# Sheet1.net
KiCad netlist of a schematic drawn in Altium Designer
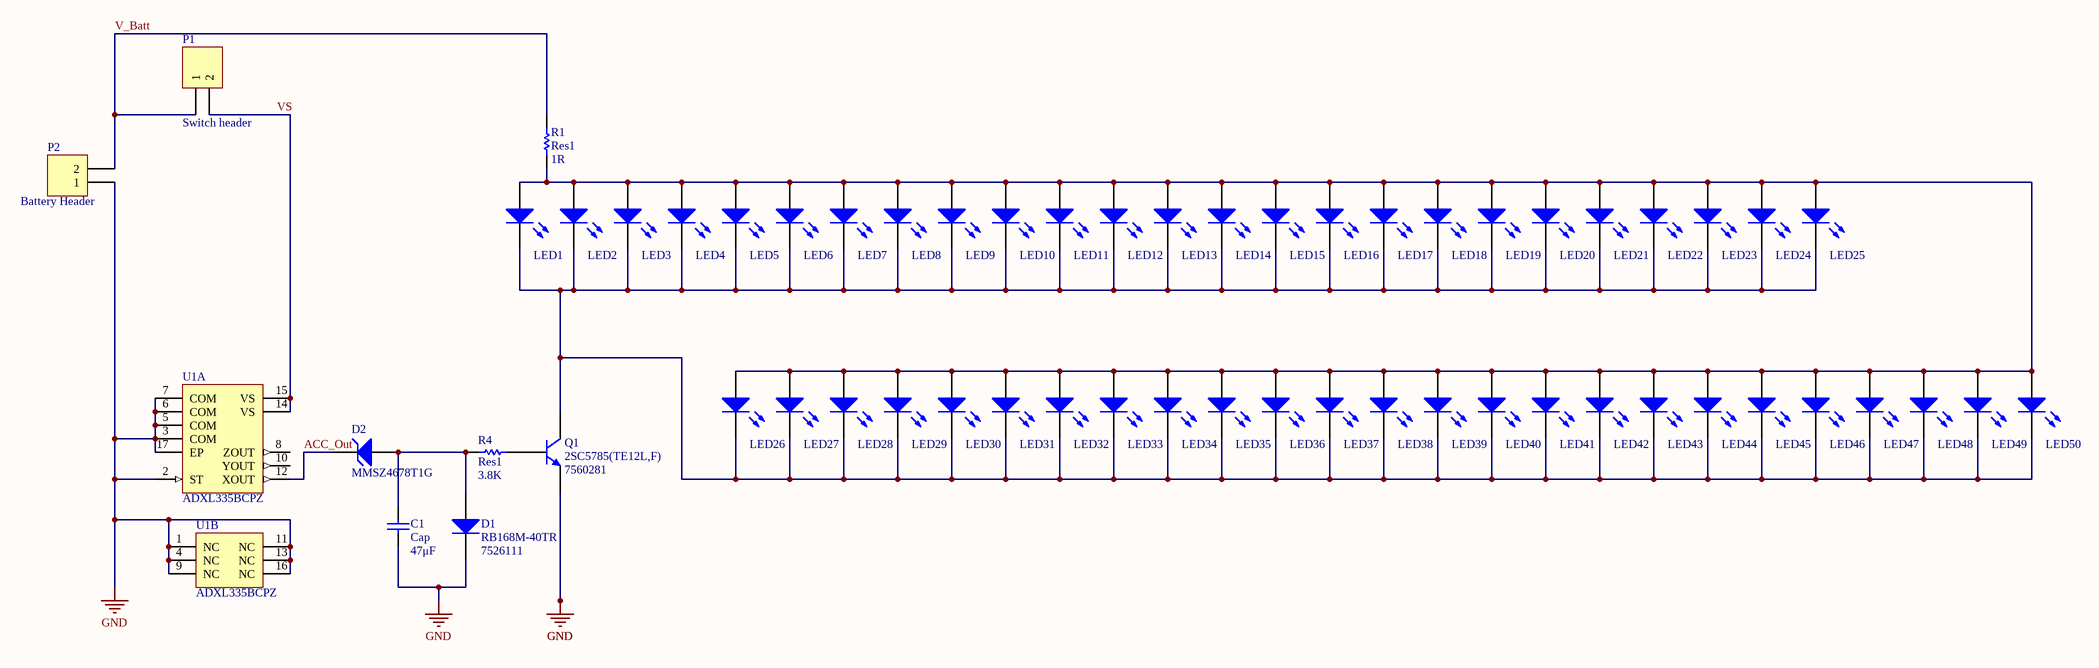
[diagram p0: Sheet1.SchDoc]

(export (version "E")
  (design (tool "Eeschema 10.0.6"))
  (components
    (comp (ref "C1")
      (value "Cap")
      (footprint "Capacitor 0603")
      (description "Capacitor")
      (fields (field (name "ALTIUM_VALUE") "47μF") (field (name "PUBLISHER") "Altium Limited"))
      (libsource (lib "Miscellaneous Devices") (part "Cap"))
    )
    (comp (ref "D1")
      (value "RB168M-40TR")
      (footprint "SODFL350X90-2N")
      (description "DIODE SCHOTTKY 40V 1A PMDU")
      (fields (field (name "MANUFACTURER") "Rohm") (field (name "SUPPLIER PART NUMBER 1") "7526111"))
      (libsource (lib "Schlib1") (part "RB168M-40TR"))
    )
    (comp (ref "D2")
      (value "MMSZ4678T1G")
      (footprint "SODFL371X135-2N")
      (description "ON SEMICONDUCTOR         MMSZ4678T1G.             ZENER DIODE, 500mW, 1.8V, SOD-123")
      (fields (field (name "MANUFACTURER") "ON Semiconductor") (field (name "TOLERANCE") "5%"))
      (libsource (lib "Schlib1") (part "MMSZ4678T1G"))
    )
    (comp (ref "LED1")
      (value "150080RS75000")
      (footprint "0805_A")
      (description "SMD mono-color Chip LED, WL-SMCW, Red")
      (fields (field (name "MANUFACTURER") "Wuerth Elektronik"))
      (libsource (lib "Altium Content Vault") (part "WE-LED_K1A2-2"))
    )
    (comp (ref "LED2")
      (value "150080RS75000")
      (footprint "0805_A")
      (description "SMD mono-color Chip LED, WL-SMCW, Red")
      (fields (field (name "MANUFACTURER") "Wuerth Elektronik"))
      (libsource (lib "Altium Content Vault") (part "WE-LED_K1A2-2"))
    )
    (comp (ref "LED3")
      (value "150080RS75000")
      (footprint "0805_A")
      (description "SMD mono-color Chip LED, WL-SMCW, Red")
      (fields (field (name "MANUFACTURER") "Wuerth Elektronik"))
      (libsource (lib "Altium Content Vault") (part "WE-LED_K1A2-2"))
    )
    (comp (ref "LED4")
      (value "150080RS75000")
      (footprint "0805_A")
      (description "SMD mono-color Chip LED, WL-SMCW, Red")
      (fields (field (name "MANUFACTURER") "Wuerth Elektronik"))
      (libsource (lib "Altium Content Vault") (part "WE-LED_K1A2-2"))
    )
    (comp (ref "LED5")
      (value "150080RS75000")
      (footprint "0805_A")
      (description "SMD mono-color Chip LED, WL-SMCW, Red")
      (fields (field (name "MANUFACTURER") "Wuerth Elektronik"))
      (libsource (lib "Altium Content Vault") (part "WE-LED_K1A2-2"))
    )
    (comp (ref "LED6")
      (value "150080RS75000")
      (footprint "0805_A")
      (description "SMD mono-color Chip LED, WL-SMCW, Red")
      (fields (field (name "MANUFACTURER") "Wuerth Elektronik"))
      (libsource (lib "Altium Content Vault") (part "WE-LED_K1A2-2"))
    )
    (comp (ref "LED7")
      (value "150080RS75000")
      (footprint "0805_A")
      (description "SMD mono-color Chip LED, WL-SMCW, Red")
      (fields (field (name "MANUFACTURER") "Wuerth Elektronik"))
      (libsource (lib "Altium Content Vault") (part "WE-LED_K1A2-2"))
    )
    (comp (ref "LED8")
      (value "150080RS75000")
      (footprint "0805_A")
      (description "SMD mono-color Chip LED, WL-SMCW, Red")
      (fields (field (name "MANUFACTURER") "Wuerth Elektronik"))
      (libsource (lib "Altium Content Vault") (part "WE-LED_K1A2-2"))
    )
    (comp (ref "LED9")
      (value "150080RS75000")
      (footprint "0805_A")
      (description "SMD mono-color Chip LED, WL-SMCW, Red")
      (fields (field (name "MANUFACTURER") "Wuerth Elektronik"))
      (libsource (lib "Altium Content Vault") (part "WE-LED_K1A2-2"))
    )
    (comp (ref "LED10")
      (value "150080RS75000")
      (footprint "0805_A")
      (description "SMD mono-color Chip LED, WL-SMCW, Red")
      (fields (field (name "MANUFACTURER") "Wuerth Elektronik"))
      (libsource (lib "Altium Content Vault") (part "WE-LED_K1A2-2"))
    )
    (comp (ref "LED11")
      (value "150080RS75000")
      (footprint "0805_A")
      (description "SMD mono-color Chip LED, WL-SMCW, Red")
      (fields (field (name "MANUFACTURER") "Wuerth Elektronik"))
      (libsource (lib "Altium Content Vault") (part "WE-LED_K1A2-2"))
    )
    (comp (ref "LED12")
      (value "150080RS75000")
      (footprint "0805_A")
      (description "SMD mono-color Chip LED, WL-SMCW, Red")
      (fields (field (name "MANUFACTURER") "Wuerth Elektronik"))
      (libsource (lib "Altium Content Vault") (part "WE-LED_K1A2-2"))
    )
    (comp (ref "LED13")
      (value "150080RS75000")
      (footprint "0805_A")
      (description "SMD mono-color Chip LED, WL-SMCW, Red")
      (fields (field (name "MANUFACTURER") "Wuerth Elektronik"))
      (libsource (lib "Altium Content Vault") (part "WE-LED_K1A2-2"))
    )
    (comp (ref "LED14")
      (value "150080RS75000")
      (footprint "0805_A")
      (description "SMD mono-color Chip LED, WL-SMCW, Red")
      (fields (field (name "MANUFACTURER") "Wuerth Elektronik"))
      (libsource (lib "Altium Content Vault") (part "WE-LED_K1A2-2"))
    )
    (comp (ref "LED15")
      (value "150080RS75000")
      (footprint "0805_A")
      (description "SMD mono-color Chip LED, WL-SMCW, Red")
      (fields (field (name "MANUFACTURER") "Wuerth Elektronik"))
      (libsource (lib "Altium Content Vault") (part "WE-LED_K1A2-2"))
    )
    (comp (ref "LED16")
      (value "150080RS75000")
      (footprint "0805_A")
      (description "SMD mono-color Chip LED, WL-SMCW, Red")
      (fields (field (name "MANUFACTURER") "Wuerth Elektronik"))
      (libsource (lib "Altium Content Vault") (part "WE-LED_K1A2-2"))
    )
    (comp (ref "LED17")
      (value "150080RS75000")
      (footprint "0805_A")
      (description "SMD mono-color Chip LED, WL-SMCW, Red")
      (fields (field (name "MANUFACTURER") "Wuerth Elektronik"))
      (libsource (lib "Altium Content Vault") (part "WE-LED_K1A2-2"))
    )
    (comp (ref "LED18")
      (value "150080RS75000")
      (footprint "0805_A")
      (description "SMD mono-color Chip LED, WL-SMCW, Red")
      (fields (field (name "MANUFACTURER") "Wuerth Elektronik"))
      (libsource (lib "Altium Content Vault") (part "WE-LED_K1A2-2"))
    )
    (comp (ref "LED19")
      (value "150080RS75000")
      (footprint "0805_A")
      (description "SMD mono-color Chip LED, WL-SMCW, Red")
      (fields (field (name "MANUFACTURER") "Wuerth Elektronik"))
      (libsource (lib "Altium Content Vault") (part "WE-LED_K1A2-2"))
    )
    (comp (ref "LED20")
      (value "150080RS75000")
      (footprint "0805_A")
      (description "SMD mono-color Chip LED, WL-SMCW, Red")
      (fields (field (name "MANUFACTURER") "Wuerth Elektronik"))
      (libsource (lib "Altium Content Vault") (part "WE-LED_K1A2-2"))
    )
    (comp (ref "LED21")
      (value "150080RS75000")
      (footprint "0805_A")
      (description "SMD mono-color Chip LED, WL-SMCW, Red")
      (fields (field (name "MANUFACTURER") "Wuerth Elektronik"))
      (libsource (lib "Altium Content Vault") (part "WE-LED_K1A2-2"))
    )
    (comp (ref "LED22")
      (value "150080RS75000")
      (footprint "0805_A")
      (description "SMD mono-color Chip LED, WL-SMCW, Red")
      (fields (field (name "MANUFACTURER") "Wuerth Elektronik"))
      (libsource (lib "Altium Content Vault") (part "WE-LED_K1A2-2"))
    )
    (comp (ref "LED23")
      (value "150080RS75000")
      (footprint "0805_A")
      (description "SMD mono-color Chip LED, WL-SMCW, Red")
      (fields (field (name "MANUFACTURER") "Wuerth Elektronik"))
      (libsource (lib "Altium Content Vault") (part "WE-LED_K1A2-2"))
    )
    (comp (ref "LED24")
      (value "150080RS75000")
      (footprint "0805_A")
      (description "SMD mono-color Chip LED, WL-SMCW, Red")
      (fields (field (name "MANUFACTURER") "Wuerth Elektronik"))
      (libsource (lib "Altium Content Vault") (part "WE-LED_K1A2-2"))
    )
    (comp (ref "LED25")
      (value "150080RS75000")
      (footprint "0805_A")
      (description "SMD mono-color Chip LED, WL-SMCW, Red")
      (fields (field (name "MANUFACTURER") "Wuerth Elektronik"))
      (libsource (lib "Altium Content Vault") (part "WE-LED_K1A2-2"))
    )
    (comp (ref "LED26")
      (value "150080RS75000")
      (footprint "0805_A")
      (description "SMD mono-color Chip LED, WL-SMCW, Red")
      (fields (field (name "MANUFACTURER") "Wuerth Elektronik"))
      (libsource (lib "Altium Content Vault") (part "WE-LED_K1A2-2"))
    )
    (comp (ref "LED27")
      (value "150080RS75000")
      (footprint "0805_A")
      (description "SMD mono-color Chip LED, WL-SMCW, Red")
      (fields (field (name "MANUFACTURER") "Wuerth Elektronik"))
      (libsource (lib "Altium Content Vault") (part "WE-LED_K1A2-2"))
    )
    (comp (ref "LED28")
      (value "150080RS75000")
      (footprint "0805_A")
      (description "SMD mono-color Chip LED, WL-SMCW, Red")
      (fields (field (name "MANUFACTURER") "Wuerth Elektronik"))
      (libsource (lib "Altium Content Vault") (part "WE-LED_K1A2-2"))
    )
    (comp (ref "LED29")
      (value "150080RS75000")
      (footprint "0805_A")
      (description "SMD mono-color Chip LED, WL-SMCW, Red")
      (fields (field (name "MANUFACTURER") "Wuerth Elektronik"))
      (libsource (lib "Altium Content Vault") (part "WE-LED_K1A2-2"))
    )
    (comp (ref "LED30")
      (value "150080RS75000")
      (footprint "0805_A")
      (description "SMD mono-color Chip LED, WL-SMCW, Red")
      (fields (field (name "MANUFACTURER") "Wuerth Elektronik"))
      (libsource (lib "Altium Content Vault") (part "WE-LED_K1A2-2"))
    )
    (comp (ref "LED31")
      (value "150080RS75000")
      (footprint "0805_A")
      (description "SMD mono-color Chip LED, WL-SMCW, Red")
      (fields (field (name "MANUFACTURER") "Wuerth Elektronik"))
      (libsource (lib "Altium Content Vault") (part "WE-LED_K1A2-2"))
    )
    (comp (ref "LED32")
      (value "150080RS75000")
      (footprint "0805_A")
      (description "SMD mono-color Chip LED, WL-SMCW, Red")
      (fields (field (name "MANUFACTURER") "Wuerth Elektronik"))
      (libsource (lib "Altium Content Vault") (part "WE-LED_K1A2-2"))
    )
    (comp (ref "LED33")
      (value "150080RS75000")
      (footprint "0805_A")
      (description "SMD mono-color Chip LED, WL-SMCW, Red")
      (fields (field (name "MANUFACTURER") "Wuerth Elektronik"))
      (libsource (lib "Altium Content Vault") (part "WE-LED_K1A2-2"))
    )
    (comp (ref "LED34")
      (value "150080RS75000")
      (footprint "0805_A")
      (description "SMD mono-color Chip LED, WL-SMCW, Red")
      (fields (field (name "MANUFACTURER") "Wuerth Elektronik"))
      (libsource (lib "Altium Content Vault") (part "WE-LED_K1A2-2"))
    )
    (comp (ref "LED35")
      (value "150080RS75000")
      (footprint "0805_A")
      (description "SMD mono-color Chip LED, WL-SMCW, Red")
      (fields (field (name "MANUFACTURER") "Wuerth Elektronik"))
      (libsource (lib "Altium Content Vault") (part "WE-LED_K1A2-2"))
    )
    (comp (ref "LED36")
      (value "150080RS75000")
      (footprint "0805_A")
      (description "SMD mono-color Chip LED, WL-SMCW, Red")
      (fields (field (name "MANUFACTURER") "Wuerth Elektronik"))
      (libsource (lib "Altium Content Vault") (part "WE-LED_K1A2-2"))
    )
    (comp (ref "LED37")
      (value "150080RS75000")
      (footprint "0805_A")
      (description "SMD mono-color Chip LED, WL-SMCW, Red")
      (fields (field (name "MANUFACTURER") "Wuerth Elektronik"))
      (libsource (lib "Altium Content Vault") (part "WE-LED_K1A2-2"))
    )
    (comp (ref "LED38")
      (value "150080RS75000")
      (footprint "0805_A")
      (description "SMD mono-color Chip LED, WL-SMCW, Red")
      (fields (field (name "MANUFACTURER") "Wuerth Elektronik"))
      (libsource (lib "Altium Content Vault") (part "WE-LED_K1A2-2"))
    )
    (comp (ref "LED39")
      (value "150080RS75000")
      (footprint "0805_A")
      (description "SMD mono-color Chip LED, WL-SMCW, Red")
      (fields (field (name "MANUFACTURER") "Wuerth Elektronik"))
      (libsource (lib "Altium Content Vault") (part "WE-LED_K1A2-2"))
    )
    (comp (ref "LED40")
      (value "150080RS75000")
      (footprint "0805_A")
      (description "SMD mono-color Chip LED, WL-SMCW, Red")
      (fields (field (name "MANUFACTURER") "Wuerth Elektronik"))
      (libsource (lib "Altium Content Vault") (part "WE-LED_K1A2-2"))
    )
    (comp (ref "LED41")
      (value "150080RS75000")
      (footprint "0805_A")
      (description "SMD mono-color Chip LED, WL-SMCW, Red")
      (fields (field (name "MANUFACTURER") "Wuerth Elektronik"))
      (libsource (lib "Altium Content Vault") (part "WE-LED_K1A2-2"))
    )
    (comp (ref "LED42")
      (value "150080RS75000")
      (footprint "0805_A")
      (description "SMD mono-color Chip LED, WL-SMCW, Red")
      (fields (field (name "MANUFACTURER") "Wuerth Elektronik"))
      (libsource (lib "Altium Content Vault") (part "WE-LED_K1A2-2"))
    )
    (comp (ref "LED43")
      (value "150080RS75000")
      (footprint "0805_A")
      (description "SMD mono-color Chip LED, WL-SMCW, Red")
      (fields (field (name "MANUFACTURER") "Wuerth Elektronik"))
      (libsource (lib "Altium Content Vault") (part "WE-LED_K1A2-2"))
    )
    (comp (ref "LED44")
      (value "150080RS75000")
      (footprint "0805_A")
      (description "SMD mono-color Chip LED, WL-SMCW, Red")
      (fields (field (name "MANUFACTURER") "Wuerth Elektronik"))
      (libsource (lib "Altium Content Vault") (part "WE-LED_K1A2-2"))
    )
    (comp (ref "LED45")
      (value "150080RS75000")
      (footprint "0805_A")
      (description "SMD mono-color Chip LED, WL-SMCW, Red")
      (fields (field (name "MANUFACTURER") "Wuerth Elektronik"))
      (libsource (lib "Altium Content Vault") (part "WE-LED_K1A2-2"))
    )
    (comp (ref "LED46")
      (value "150080RS75000")
      (footprint "0805_A")
      (description "SMD mono-color Chip LED, WL-SMCW, Red")
      (fields (field (name "MANUFACTURER") "Wuerth Elektronik"))
      (libsource (lib "Altium Content Vault") (part "WE-LED_K1A2-2"))
    )
    (comp (ref "LED47")
      (value "150080RS75000")
      (footprint "0805_A")
      (description "SMD mono-color Chip LED, WL-SMCW, Red")
      (fields (field (name "MANUFACTURER") "Wuerth Elektronik"))
      (libsource (lib "Altium Content Vault") (part "WE-LED_K1A2-2"))
    )
    (comp (ref "LED48")
      (value "150080RS75000")
      (footprint "0805_A")
      (description "SMD mono-color Chip LED, WL-SMCW, Red")
      (fields (field (name "MANUFACTURER") "Wuerth Elektronik"))
      (libsource (lib "Altium Content Vault") (part "WE-LED_K1A2-2"))
    )
    (comp (ref "LED49")
      (value "150080RS75000")
      (footprint "0805_A")
      (description "SMD mono-color Chip LED, WL-SMCW, Red")
      (fields (field (name "MANUFACTURER") "Wuerth Elektronik"))
      (libsource (lib "Altium Content Vault") (part "WE-LED_K1A2-2"))
    )
    (comp (ref "LED50")
      (value "150080RS75000")
      (footprint "0805_A")
      (description "SMD mono-color Chip LED, WL-SMCW, Red")
      (fields (field (name "MANUFACTURER") "Wuerth Elektronik"))
      (libsource (lib "Altium Content Vault") (part "WE-LED_K1A2-2"))
    )
    (comp (ref "P1")
      (value "Switch header")
      (footprint "HDR1X2")
      (description "Header, 2-Pin")
      (fields (field (name "PUBLISHER") "Altium Limited"))
      (libsource (lib "") (part "Header 2_1"))
    )
    (comp (ref "P2")
      (value "Battery Header")
      (footprint "HDR1X2")
      (description "Header, 2-Pin")
      (fields (field (name "PUBLISHER") "Altium Limited"))
      (libsource (lib "Miscellaneous Connectors") (part "Header 2"))
    )
    (comp (ref "Q1")
      (value "2SC5785(TE12L,F)")
      (footprint "SOT89-150P410X160-3N")
      (description "NPN Bipolar Transistor, 2 A, 10 V, 3-Pin SC-62")
      (fields (field (name "MANUFACTURER") "Toshiba") (field (name "SUPPLIER PART NUMBER 1") "7560281"))
      (libsource (lib "Schlib1") (part "2SC5785(TE12L,F)"))
    )
    (comp (ref "R1")
      (value "Res1")
      (footprint "Resistor 1206")
      (description "Resistor")
      (fields (field (name "ALTIUM_VALUE") "1R") (field (name "PUBLISHER") "Altium Limited"))
      (libsource (lib "Miscellaneous Devices") (part "Res1"))
    )
    (comp (ref "R4")
      (value "Res1")
      (footprint "Resistor 1206")
      (description "Resistor")
      (fields (field (name "ALTIUM_VALUE") "3.8K") (field (name "PUBLISHER") "Altium Limited"))
      (libsource (lib "Miscellaneous Devices") (part "Res1"))
    )
    (comp (ref "U1")
      (value "ADXL335BCPZ")
      (footprint "ADI-CP-16-14_L")
      (fields (field (name "MANUFACTURER") "Analog Devices"))
      (libsource (lib "Altium Content Vault") (part "ADI-ADXL3XX-CP-16-XX"))
    )
  )
  (nets
    (net (code "1") (name "/ACC_Out") (class "Default")
      (node (ref "D2") (pin "1") (pinfunction "K_1") (pintype "passive"))
      (node (ref "U1") (pin "12") (pinfunction "XOUT_12") (pintype "output"))
    )
    (net (code "2") (name "/VS") (class "Default")
      (node (ref "P1") (pin "2") (pinfunction "2_2") (pintype "passive"))
      (node (ref "U1") (pin "14") (pinfunction "VS_14") (pintype "power_in"))
      (node (ref "U1") (pin "15") (pinfunction "VS_15") (pintype "power_in"))
    )
    (net (code "3") (name "/V_Batt") (class "Default")
      (node (ref "P1") (pin "1") (pinfunction "1_1") (pintype "passive"))
      (node (ref "P2") (pin "2") (pinfunction "2_2") (pintype "passive"))
      (node (ref "R1") (pin "2") (pinfunction "2_2") (pintype "passive"))
    )
    (net (code "4") (name "GND") (class "Default")
      (node (ref "C1") (pin "1") (pinfunction "1_1") (pintype "passive"))
      (node (ref "D1") (pin "2") (pinfunction "K_2") (pintype "passive"))
      (node (ref "P2") (pin "1") (pinfunction "1_1") (pintype "passive"))
      (node (ref "Q1") (pin "3") (pinfunction "E_3") (pintype "passive"))
      (node (ref "U1") (pin "1") (pinfunction "NC_1") (pintype "passive"))
      (node (ref "U1") (pin "11") (pinfunction "NC_11") (pintype "passive"))
      (node (ref "U1") (pin "13") (pinfunction "NC_13") (pintype "passive"))
      (node (ref "U1") (pin "16") (pinfunction "NC_16") (pintype "passive"))
      (node (ref "U1") (pin "17") (pinfunction "EP_17") (pintype "passive"))
      (node (ref "U1") (pin "2") (pinfunction "ST_2") (pintype "input"))
      (node (ref "U1") (pin "3") (pinfunction "COM_3") (pintype "power_in"))
      (node (ref "U1") (pin "4") (pinfunction "NC_4") (pintype "passive"))
      (node (ref "U1") (pin "5") (pinfunction "COM_5") (pintype "power_in"))
      (node (ref "U1") (pin "6") (pinfunction "COM_6") (pintype "power_in"))
      (node (ref "U1") (pin "7") (pinfunction "COM_7") (pintype "power_in"))
      (node (ref "U1") (pin "9") (pinfunction "NC_9") (pintype "passive"))
    )
    (net (code "5") (name "Net-(D1-A)") (class "Default")
      (node (ref "C1") (pin "2") (pinfunction "2_2") (pintype "passive"))
      (node (ref "D1") (pin "1") (pinfunction "A_1") (pintype "passive"))
      (node (ref "D2") (pin "2") (pinfunction "A_2") (pintype "passive"))
      (node (ref "R4") (pin "1") (pinfunction "1_1") (pintype "passive"))
    )
    (net (code "6") (name "Net-(LED1-A)") (class "Default")
      (node (ref "LED1") (pin "2") (pinfunction "A_2") (pintype "passive"))
      (node (ref "LED10") (pin "2") (pinfunction "A_2") (pintype "passive"))
      (node (ref "LED11") (pin "2") (pinfunction "A_2") (pintype "passive"))
      (node (ref "LED12") (pin "2") (pinfunction "A_2") (pintype "passive"))
      (node (ref "LED13") (pin "2") (pinfunction "A_2") (pintype "passive"))
      (node (ref "LED14") (pin "2") (pinfunction "A_2") (pintype "passive"))
      (node (ref "LED15") (pin "2") (pinfunction "A_2") (pintype "passive"))
      (node (ref "LED16") (pin "2") (pinfunction "A_2") (pintype "passive"))
      (node (ref "LED17") (pin "2") (pinfunction "A_2") (pintype "passive"))
      (node (ref "LED18") (pin "2") (pinfunction "A_2") (pintype "passive"))
      (node (ref "LED19") (pin "2") (pinfunction "A_2") (pintype "passive"))
      (node (ref "LED2") (pin "2") (pinfunction "A_2") (pintype "passive"))
      (node (ref "LED20") (pin "2") (pinfunction "A_2") (pintype "passive"))
      (node (ref "LED21") (pin "2") (pinfunction "A_2") (pintype "passive"))
      (node (ref "LED22") (pin "2") (pinfunction "A_2") (pintype "passive"))
      (node (ref "LED23") (pin "2") (pinfunction "A_2") (pintype "passive"))
      (node (ref "LED24") (pin "2") (pinfunction "A_2") (pintype "passive"))
      (node (ref "LED25") (pin "2") (pinfunction "A_2") (pintype "passive"))
      (node (ref "LED26") (pin "2") (pinfunction "A_2") (pintype "passive"))
      (node (ref "LED27") (pin "2") (pinfunction "A_2") (pintype "passive"))
      (node (ref "LED28") (pin "2") (pinfunction "A_2") (pintype "passive"))
      (node (ref "LED29") (pin "2") (pinfunction "A_2") (pintype "passive"))
      (node (ref "LED3") (pin "2") (pinfunction "A_2") (pintype "passive"))
      (node (ref "LED30") (pin "2") (pinfunction "A_2") (pintype "passive"))
      (node (ref "LED31") (pin "2") (pinfunction "A_2") (pintype "passive"))
      (node (ref "LED32") (pin "2") (pinfunction "A_2") (pintype "passive"))
      (node (ref "LED33") (pin "2") (pinfunction "A_2") (pintype "passive"))
      (node (ref "LED34") (pin "2") (pinfunction "A_2") (pintype "passive"))
      (node (ref "LED35") (pin "2") (pinfunction "A_2") (pintype "passive"))
      (node (ref "LED36") (pin "2") (pinfunction "A_2") (pintype "passive"))
      (node (ref "LED37") (pin "2") (pinfunction "A_2") (pintype "passive"))
      (node (ref "LED38") (pin "2") (pinfunction "A_2") (pintype "passive"))
      (node (ref "LED39") (pin "2") (pinfunction "A_2") (pintype "passive"))
      (node (ref "LED4") (pin "2") (pinfunction "A_2") (pintype "passive"))
      (node (ref "LED40") (pin "2") (pinfunction "A_2") (pintype "passive"))
      (node (ref "LED41") (pin "2") (pinfunction "A_2") (pintype "passive"))
      (node (ref "LED42") (pin "2") (pinfunction "A_2") (pintype "passive"))
      (node (ref "LED43") (pin "2") (pinfunction "A_2") (pintype "passive"))
      (node (ref "LED44") (pin "2") (pinfunction "A_2") (pintype "passive"))
      (node (ref "LED45") (pin "2") (pinfunction "A_2") (pintype "passive"))
      (node (ref "LED46") (pin "2") (pinfunction "A_2") (pintype "passive"))
      (node (ref "LED47") (pin "2") (pinfunction "A_2") (pintype "passive"))
      (node (ref "LED48") (pin "2") (pinfunction "A_2") (pintype "passive"))
      (node (ref "LED49") (pin "2") (pinfunction "A_2") (pintype "passive"))
      (node (ref "LED5") (pin "2") (pinfunction "A_2") (pintype "passive"))
      (node (ref "LED50") (pin "2") (pinfunction "A_2") (pintype "passive"))
      (node (ref "LED6") (pin "2") (pinfunction "A_2") (pintype "passive"))
      (node (ref "LED7") (pin "2") (pinfunction "A_2") (pintype "passive"))
      (node (ref "LED8") (pin "2") (pinfunction "A_2") (pintype "passive"))
      (node (ref "LED9") (pin "2") (pinfunction "A_2") (pintype "passive"))
      (node (ref "R1") (pin "1") (pinfunction "1_1") (pintype "passive"))
    )
    (net (code "7") (name "Net-(LED1-K)") (class "Default")
      (node (ref "LED1") (pin "1") (pinfunction "K_1") (pintype "passive"))
      (node (ref "LED10") (pin "1") (pinfunction "K_1") (pintype "passive"))
      (node (ref "LED11") (pin "1") (pinfunction "K_1") (pintype "passive"))
      (node (ref "LED12") (pin "1") (pinfunction "K_1") (pintype "passive"))
      (node (ref "LED13") (pin "1") (pinfunction "K_1") (pintype "passive"))
      (node (ref "LED14") (pin "1") (pinfunction "K_1") (pintype "passive"))
      (node (ref "LED15") (pin "1") (pinfunction "K_1") (pintype "passive"))
      (node (ref "LED16") (pin "1") (pinfunction "K_1") (pintype "passive"))
      (node (ref "LED17") (pin "1") (pinfunction "K_1") (pintype "passive"))
      (node (ref "LED18") (pin "1") (pinfunction "K_1") (pintype "passive"))
      (node (ref "LED19") (pin "1") (pinfunction "K_1") (pintype "passive"))
      (node (ref "LED2") (pin "1") (pinfunction "K_1") (pintype "passive"))
      (node (ref "LED20") (pin "1") (pinfunction "K_1") (pintype "passive"))
      (node (ref "LED21") (pin "1") (pinfunction "K_1") (pintype "passive"))
      (node (ref "LED22") (pin "1") (pinfunction "K_1") (pintype "passive"))
      (node (ref "LED23") (pin "1") (pinfunction "K_1") (pintype "passive"))
      (node (ref "LED24") (pin "1") (pinfunction "K_1") (pintype "passive"))
      (node (ref "LED25") (pin "1") (pinfunction "K_1") (pintype "passive"))
      (node (ref "LED26") (pin "1") (pinfunction "K_1") (pintype "passive"))
      (node (ref "LED27") (pin "1") (pinfunction "K_1") (pintype "passive"))
      (node (ref "LED28") (pin "1") (pinfunction "K_1") (pintype "passive"))
      (node (ref "LED29") (pin "1") (pinfunction "K_1") (pintype "passive"))
      (node (ref "LED3") (pin "1") (pinfunction "K_1") (pintype "passive"))
      (node (ref "LED30") (pin "1") (pinfunction "K_1") (pintype "passive"))
      (node (ref "LED31") (pin "1") (pinfunction "K_1") (pintype "passive"))
      (node (ref "LED32") (pin "1") (pinfunction "K_1") (pintype "passive"))
      (node (ref "LED33") (pin "1") (pinfunction "K_1") (pintype "passive"))
      (node (ref "LED34") (pin "1") (pinfunction "K_1") (pintype "passive"))
      (node (ref "LED35") (pin "1") (pinfunction "K_1") (pintype "passive"))
      (node (ref "LED36") (pin "1") (pinfunction "K_1") (pintype "passive"))
      (node (ref "LED37") (pin "1") (pinfunction "K_1") (pintype "passive"))
      (node (ref "LED38") (pin "1") (pinfunction "K_1") (pintype "passive"))
      (node (ref "LED39") (pin "1") (pinfunction "K_1") (pintype "passive"))
      (node (ref "LED4") (pin "1") (pinfunction "K_1") (pintype "passive"))
      (node (ref "LED40") (pin "1") (pinfunction "K_1") (pintype "passive"))
      (node (ref "LED41") (pin "1") (pinfunction "K_1") (pintype "passive"))
      (node (ref "LED42") (pin "1") (pinfunction "K_1") (pintype "passive"))
      (node (ref "LED43") (pin "1") (pinfunction "K_1") (pintype "passive"))
      (node (ref "LED44") (pin "1") (pinfunction "K_1") (pintype "passive"))
      (node (ref "LED45") (pin "1") (pinfunction "K_1") (pintype "passive"))
      (node (ref "LED46") (pin "1") (pinfunction "K_1") (pintype "passive"))
      (node (ref "LED47") (pin "1") (pinfunction "K_1") (pintype "passive"))
      (node (ref "LED48") (pin "1") (pinfunction "K_1") (pintype "passive"))
      (node (ref "LED49") (pin "1") (pinfunction "K_1") (pintype "passive"))
      (node (ref "LED5") (pin "1") (pinfunction "K_1") (pintype "passive"))
      (node (ref "LED50") (pin "1") (pinfunction "K_1") (pintype "passive"))
      (node (ref "LED6") (pin "1") (pinfunction "K_1") (pintype "passive"))
      (node (ref "LED7") (pin "1") (pinfunction "K_1") (pintype "passive"))
      (node (ref "LED8") (pin "1") (pinfunction "K_1") (pintype "passive"))
      (node (ref "LED9") (pin "1") (pinfunction "K_1") (pintype "passive"))
      (node (ref "Q1") (pin "2") (pinfunction "C_2") (pintype "passive"))
    )
    (net (code "8") (name "Net-(Q1-B)") (class "Default")
      (node (ref "Q1") (pin "1") (pinfunction "B_1") (pintype "passive"))
      (node (ref "R4") (pin "2") (pinfunction "2_2") (pintype "passive"))
    )
    (net (code "9") (name "unconnected-(U1A-YOUT-Pad10)") (class "Default")
      (node (ref "U1") (pin "10") (pinfunction "YOUT_10") (pintype "output"))
    )
    (net (code "10") (name "unconnected-(U1A-ZOUT-Pad8)") (class "Default")
      (node (ref "U1") (pin "8") (pinfunction "ZOUT_8") (pintype "output"))
    )
  )
)
